# dtb-218-AW1.net
KiCad netlist of a schematic drawn in Altium Designer
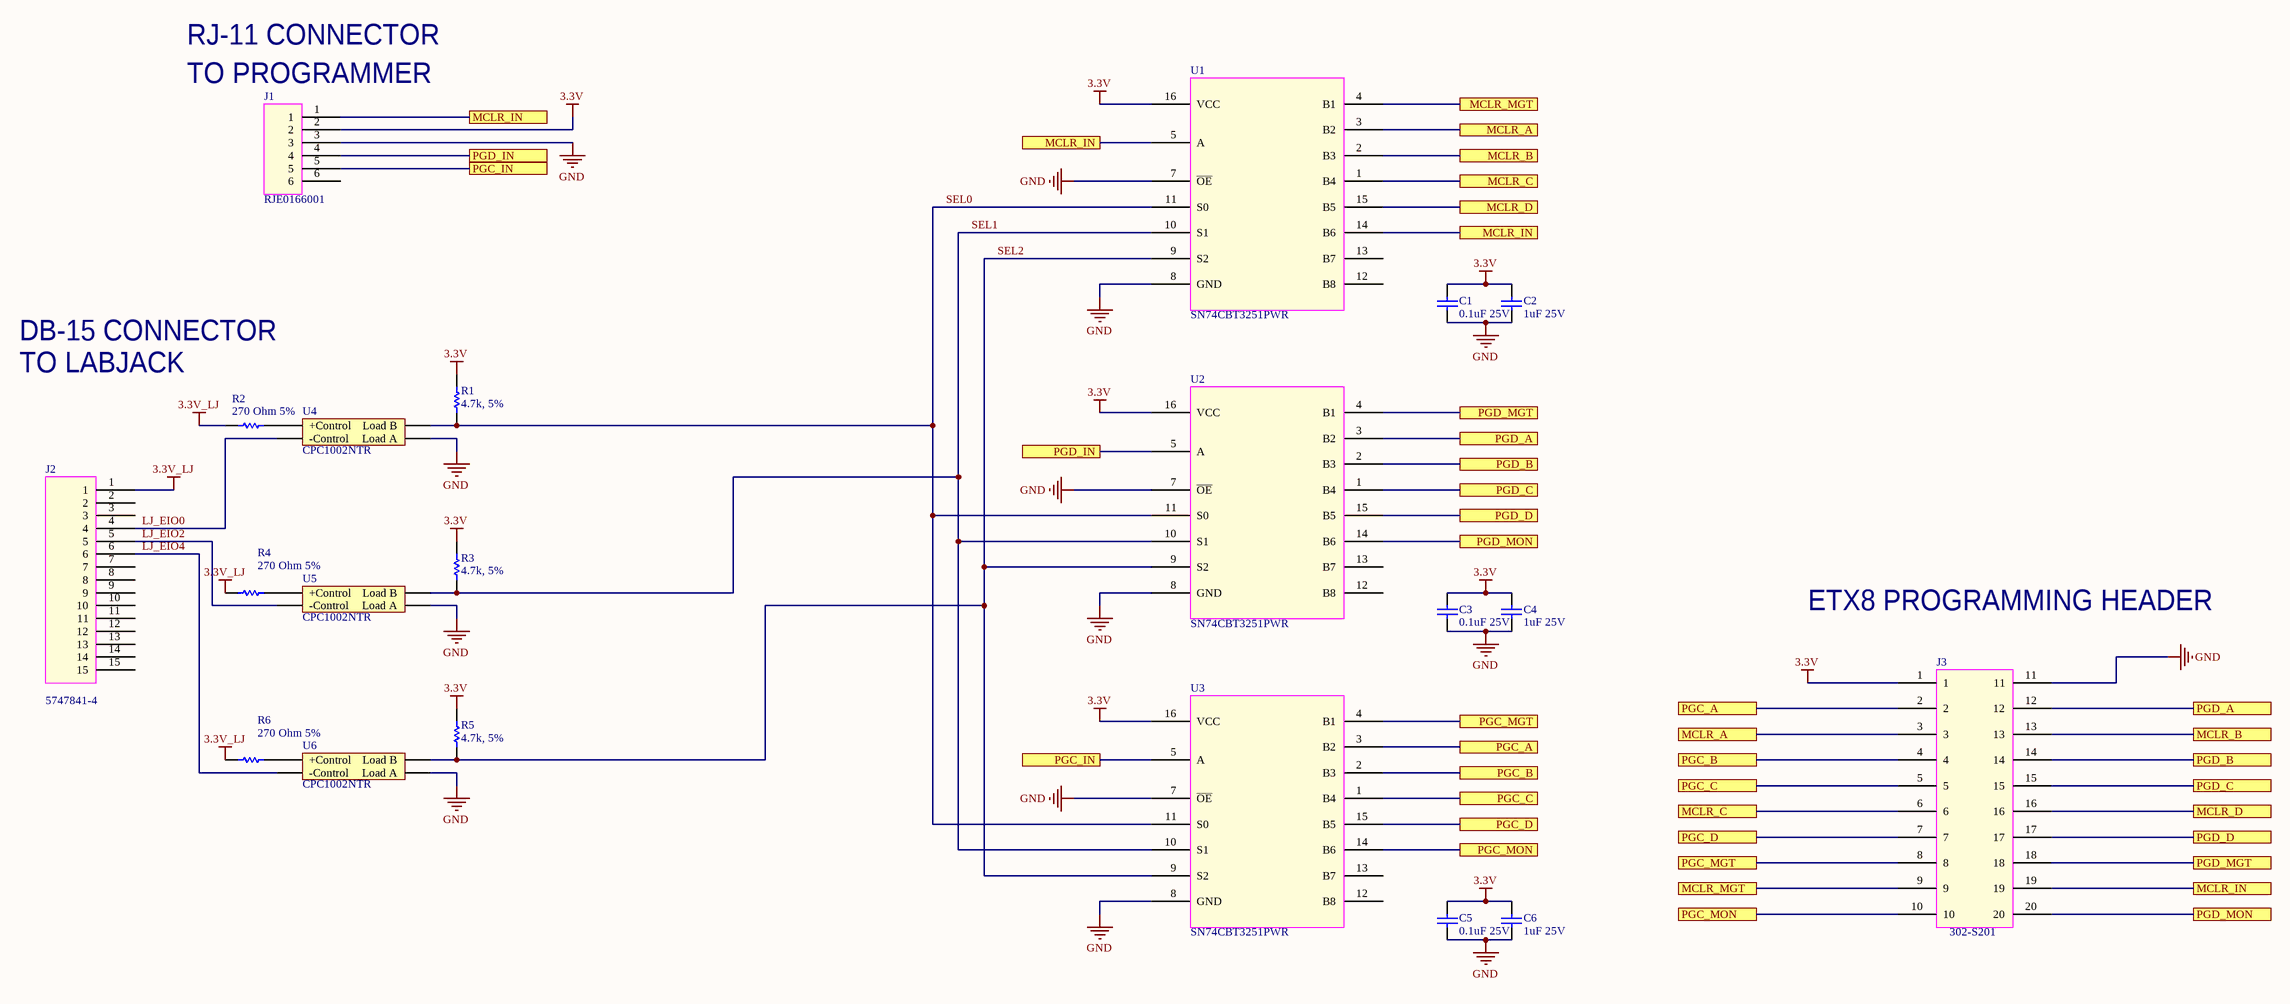
[diagram p0: dtb-218-AW1.SchDoc]

(export (version "E")
  (design (tool "Eeschema 10.0.6"))
  (components
    (comp (ref "C1")
      (value "0.1uF 25V")
      (footprint "Standard VoltServer 0603 Capacitor Footprint")
      (description "CAP CER 0.1UF 25V 10% X7R 0603")
      (fields (field (name "MANUFACTURER") "Samsung") (field (name "Comment") "CL10B104KA8NNNC"))
      (libsource (lib "VoltServer Library") (part "CL10B104KA8NNNC"))
    )
    (comp (ref "C2")
      (value "1uF 25V")
      (footprint "Standard VoltServer 0603 Capacitor Footprint")
      (description "CAP CER 1UF 25V 10% X7R 0603")
      (fields (field (name "MANUFACTURER") "Samsung") (field (name "Comment") "CL10B105KA8NNNC"))
      (libsource (lib "VoltServer Library") (part "CL10B105KA8NNNC"))
    )
    (comp (ref "C3")
      (value "0.1uF 25V")
      (footprint "Standard VoltServer 0603 Capacitor Footprint")
      (description "CAP CER 0.1UF 25V 10% X7R 0603")
      (fields (field (name "MANUFACTURER") "Samsung") (field (name "Comment") "CL10B104KA8NNNC"))
      (libsource (lib "VoltServer Library") (part "CL10B104KA8NNNC"))
    )
    (comp (ref "C4")
      (value "1uF 25V")
      (footprint "Standard VoltServer 0603 Capacitor Footprint")
      (description "CAP CER 1UF 25V 10% X7R 0603")
      (fields (field (name "MANUFACTURER") "Samsung") (field (name "Comment") "CL10B105KA8NNNC"))
      (libsource (lib "VoltServer Library") (part "CL10B105KA8NNNC"))
    )
    (comp (ref "C5")
      (value "0.1uF 25V")
      (footprint "Standard VoltServer 0603 Capacitor Footprint")
      (description "CAP CER 0.1UF 25V 10% X7R 0603")
      (fields (field (name "MANUFACTURER") "Samsung") (field (name "Comment") "CL10B104KA8NNNC"))
      (libsource (lib "VoltServer Library") (part "CL10B104KA8NNNC"))
    )
    (comp (ref "C6")
      (value "1uF 25V")
      (footprint "Standard VoltServer 0603 Capacitor Footprint")
      (description "CAP CER 1UF 25V 10% X7R 0603")
      (fields (field (name "MANUFACTURER") "Samsung") (field (name "Comment") "CL10B105KA8NNNC"))
      (libsource (lib "VoltServer Library") (part "CL10B105KA8NNNC"))
    )
    (comp (ref "J1")
      (value "RJE0166001")
      (footprint "RJE0166001")
      (description "CONN MOD JACK 6P6C R/A UNSHLD")
      (fields (field (name "MANUFACTURER") "Amphenol"))
      (libsource (lib "Allen_Integrated_Library") (part "RJE0166001"))
    )
    (comp (ref "J2")
      (value "5747841-4")
      (footprint "5747841-4")
      (description "CONN D-SUB PLUG 15POS R/A SOLDER")
      (fields (field (name "MANUFACTURER") "TE Connectivity"))
      (libsource (lib "Allen_Integrated_Library") (part "5747841-4"))
    )
    (comp (ref "J3")
      (value "302-S201")
      (footprint "302-S201")
      (description "20 Positions Header, Shrouded Connector 0.100\"")
      (fields (field (name "MANUFACTURER") "On Shore Technology"))
      (libsource (lib "AllenLibrary") (part "302-S201"))
    )
    (comp (ref "R1")
      (value "4.7k, 5%")
      (footprint "Standard VoltServer 0603 Resistor Footprint")
      (description "RES SMD 4.7K OHM 5% 1/10W 0603")
      (fields (field (name "MANUFACTURER") "Samsung") (field (name "Comment") "RC1608J472CS"))
      (libsource (lib "VoltServer Library") (part "RC1608F105CS"))
    )
    (comp (ref "R2")
      (value "270 Ohm 5%")
      (footprint "Standard VoltServer 0603 Resistor Footprint")
      (description "RES SMD 270 OHM 5% 1/10W 0603")
      (fields (field (name "MANUFACTURER") "Samsung") (field (name "Comment") "RC1608J271CS"))
      (libsource (lib "VoltServer Library") (part "RC1608J271CS"))
    )
    (comp (ref "R3")
      (value "4.7k, 5%")
      (footprint "Standard VoltServer 0603 Resistor Footprint")
      (description "RES SMD 4.7K OHM 5% 1/10W 0603")
      (fields (field (name "MANUFACTURER") "Samsung") (field (name "Comment") "RC1608J472CS"))
      (libsource (lib "VoltServer Library") (part "RC1608F105CS"))
    )
    (comp (ref "R4")
      (value "270 Ohm 5%")
      (footprint "Standard VoltServer 0603 Resistor Footprint")
      (description "RES SMD 270 OHM 5% 1/10W 0603")
      (fields (field (name "MANUFACTURER") "Samsung") (field (name "Comment") "RC1608J271CS"))
      (libsource (lib "VoltServer Library") (part "RC1608J271CS"))
    )
    (comp (ref "R5")
      (value "4.7k, 5%")
      (footprint "Standard VoltServer 0603 Resistor Footprint")
      (description "RES SMD 4.7K OHM 5% 1/10W 0603")
      (fields (field (name "MANUFACTURER") "Samsung") (field (name "Comment") "RC1608J472CS"))
      (libsource (lib "VoltServer Library") (part "RC1608F105CS"))
    )
    (comp (ref "R6")
      (value "270 Ohm 5%")
      (footprint "Standard VoltServer 0603 Resistor Footprint")
      (description "RES SMD 270 OHM 5% 1/10W 0603")
      (fields (field (name "MANUFACTURER") "Samsung") (field (name "Comment") "RC1608J271CS"))
      (libsource (lib "VoltServer Library") (part "RC1608J271CS"))
    )
    (comp (ref "U1")
      (value "SN74CBT3251PWR")
      (footprint "SN74CBT3251PWR")
      (description "IC 1-OF-8 FET MUX/DEMUX 16-TSSOP")
      (fields (field (name "MANUFACTURER") "Texas Instruments"))
      (libsource (lib "Allen_Integrated_Library") (part "SN74CBT3251PWR"))
    )
    (comp (ref "U2")
      (value "SN74CBT3251PWR")
      (footprint "SN74CBT3251PWR")
      (description "IC 1-OF-8 FET MUX/DEMUX 16-TSSOP")
      (fields (field (name "MANUFACTURER") "Texas Instruments"))
      (libsource (lib "Allen_Integrated_Library") (part "SN74CBT3251PWR"))
    )
    (comp (ref "U3")
      (value "SN74CBT3251PWR")
      (footprint "SN74CBT3251PWR")
      (description "IC 1-OF-8 FET MUX/DEMUX 16-TSSOP")
      (fields (field (name "MANUFACTURER") "Texas Instruments"))
      (libsource (lib "Allen_Integrated_Library") (part "SN74CBT3251PWR"))
    )
    (comp (ref "U4")
      (value "CPC1002NTR")
      (footprint "CPC1002NTR")
      (description "RELAY OPTOMOS 700MA 4-SOP")
      (fields (field (name "MANUFACTURER") "IXYS Integrated Circuits Division"))
      (libsource (lib "VoltServer Library") (part "CPC1002NTR"))
    )
    (comp (ref "U5")
      (value "CPC1002NTR")
      (footprint "CPC1002NTR")
      (description "RELAY OPTOMOS 700MA 4-SOP")
      (fields (field (name "MANUFACTURER") "IXYS Integrated Circuits Division"))
      (libsource (lib "VoltServer Library") (part "CPC1002NTR"))
    )
    (comp (ref "U6")
      (value "CPC1002NTR")
      (footprint "CPC1002NTR")
      (description "RELAY OPTOMOS 700MA 4-SOP")
      (fields (field (name "MANUFACTURER") "IXYS Integrated Circuits Division"))
      (libsource (lib "VoltServer Library") (part "CPC1002NTR"))
    )
  )
  (nets
    (net (code "1") (name "/LJ_EIO0") (class "Default")
      (node (ref "J2") (pin "4") (pinfunction "4_4") (pintype "passive"))
      (node (ref "U4") (pin "2") (pinfunction "-Control_2") (pintype "passive"))
    )
    (net (code "2") (name "/LJ_EIO2") (class "Default")
      (node (ref "J2") (pin "5") (pinfunction "5_5") (pintype "passive"))
      (node (ref "U5") (pin "2") (pinfunction "-Control_2") (pintype "passive"))
    )
    (net (code "3") (name "/LJ_EIO4") (class "Default")
      (node (ref "J2") (pin "6") (pinfunction "6_6") (pintype "passive"))
      (node (ref "U6") (pin "2") (pinfunction "-Control_2") (pintype "passive"))
    )
    (net (code "4") (name "/MCLR_A") (class "Default")
      (node (ref "J3") (pin "3") (pinfunction "3_3") (pintype "passive"))
      (node (ref "U1") (pin "3") (pinfunction "B2_3") (pintype "passive"))
    )
    (net (code "5") (name "/MCLR_B") (class "Default")
      (node (ref "J3") (pin "13") (pinfunction "13_13") (pintype "passive"))
      (node (ref "U1") (pin "2") (pinfunction "B3_2") (pintype "passive"))
    )
    (net (code "6") (name "/MCLR_C") (class "Default")
      (node (ref "J3") (pin "6") (pinfunction "6_6") (pintype "passive"))
      (node (ref "U1") (pin "1") (pinfunction "B4_1") (pintype "passive"))
    )
    (net (code "7") (name "/MCLR_D") (class "Default")
      (node (ref "J3") (pin "16") (pinfunction "16_16") (pintype "passive"))
      (node (ref "U1") (pin "15") (pinfunction "B5_15") (pintype "passive"))
    )
    (net (code "8") (name "/MCLR_IN") (class "Default")
      (node (ref "J1") (pin "1") (pinfunction "1_1") (pintype "passive"))
      (node (ref "J3") (pin "19") (pinfunction "19_19") (pintype "passive"))
      (node (ref "U1") (pin "14") (pinfunction "B6_14") (pintype "passive"))
      (node (ref "U1") (pin "5") (pinfunction "A_5") (pintype "passive"))
    )
    (net (code "9") (name "/MCLR_MGT") (class "Default")
      (node (ref "J3") (pin "9") (pinfunction "9_9") (pintype "passive"))
      (node (ref "U1") (pin "4") (pinfunction "B1_4") (pintype "passive"))
    )
    (net (code "10") (name "/PGC_A") (class "Default")
      (node (ref "J3") (pin "2") (pinfunction "2_2") (pintype "passive"))
      (node (ref "U3") (pin "3") (pinfunction "B2_3") (pintype "passive"))
    )
    (net (code "11") (name "/PGC_B") (class "Default")
      (node (ref "J3") (pin "4") (pinfunction "4_4") (pintype "passive"))
      (node (ref "U3") (pin "2") (pinfunction "B3_2") (pintype "passive"))
    )
    (net (code "12") (name "/PGC_C") (class "Default")
      (node (ref "J3") (pin "5") (pinfunction "5_5") (pintype "passive"))
      (node (ref "U3") (pin "1") (pinfunction "B4_1") (pintype "passive"))
    )
    (net (code "13") (name "/PGC_D") (class "Default")
      (node (ref "J3") (pin "7") (pinfunction "7_7") (pintype "passive"))
      (node (ref "U3") (pin "15") (pinfunction "B5_15") (pintype "passive"))
    )
    (net (code "14") (name "/PGC_IN") (class "Default")
      (node (ref "J1") (pin "5") (pinfunction "5_5") (pintype "passive"))
      (node (ref "U3") (pin "5") (pinfunction "A_5") (pintype "passive"))
    )
    (net (code "15") (name "/PGC_MGT") (class "Default")
      (node (ref "J3") (pin "8") (pinfunction "8_8") (pintype "passive"))
      (node (ref "U3") (pin "4") (pinfunction "B1_4") (pintype "passive"))
    )
    (net (code "16") (name "/PGC_MON") (class "Default")
      (node (ref "J3") (pin "10") (pinfunction "10_10") (pintype "passive"))
      (node (ref "U3") (pin "14") (pinfunction "B6_14") (pintype "passive"))
    )
    (net (code "17") (name "/PGD_A") (class "Default")
      (node (ref "J3") (pin "12") (pinfunction "12_12") (pintype "passive"))
      (node (ref "U2") (pin "3") (pinfunction "B2_3") (pintype "passive"))
    )
    (net (code "18") (name "/PGD_B") (class "Default")
      (node (ref "J3") (pin "14") (pinfunction "14_14") (pintype "passive"))
      (node (ref "U2") (pin "2") (pinfunction "B3_2") (pintype "passive"))
    )
    (net (code "19") (name "/PGD_C") (class "Default")
      (node (ref "J3") (pin "15") (pinfunction "15_15") (pintype "passive"))
      (node (ref "U2") (pin "1") (pinfunction "B4_1") (pintype "passive"))
    )
    (net (code "20") (name "/PGD_D") (class "Default")
      (node (ref "J3") (pin "17") (pinfunction "17_17") (pintype "passive"))
      (node (ref "U2") (pin "15") (pinfunction "B5_15") (pintype "passive"))
    )
    (net (code "21") (name "/PGD_IN") (class "Default")
      (node (ref "J1") (pin "4") (pinfunction "4_4") (pintype "passive"))
      (node (ref "U2") (pin "5") (pinfunction "A_5") (pintype "passive"))
    )
    (net (code "22") (name "/PGD_MGT") (class "Default")
      (node (ref "J3") (pin "18") (pinfunction "18_18") (pintype "passive"))
      (node (ref "U2") (pin "4") (pinfunction "B1_4") (pintype "passive"))
    )
    (net (code "23") (name "/PGD_MON") (class "Default")
      (node (ref "J3") (pin "20") (pinfunction "20_20") (pintype "passive"))
      (node (ref "U2") (pin "14") (pinfunction "B6_14") (pintype "passive"))
    )
    (net (code "24") (name "/SEL0") (class "Default")
      (node (ref "R1") (pin "2") (pinfunction "2_2") (pintype "passive"))
      (node (ref "U1") (pin "11") (pinfunction "S0_11") (pintype "passive"))
      (node (ref "U2") (pin "11") (pinfunction "S0_11") (pintype "passive"))
      (node (ref "U3") (pin "11") (pinfunction "S0_11") (pintype "passive"))
      (node (ref "U4") (pin "4") (pinfunction "Load_B_4") (pintype "passive"))
    )
    (net (code "25") (name "/SEL1") (class "Default")
      (node (ref "R3") (pin "2") (pinfunction "2_2") (pintype "passive"))
      (node (ref "U1") (pin "10") (pinfunction "S1_10") (pintype "passive"))
      (node (ref "U2") (pin "10") (pinfunction "S1_10") (pintype "passive"))
      (node (ref "U3") (pin "10") (pinfunction "S1_10") (pintype "passive"))
      (node (ref "U5") (pin "4") (pinfunction "Load_B_4") (pintype "passive"))
    )
    (net (code "26") (name "/SEL2") (class "Default")
      (node (ref "R5") (pin "2") (pinfunction "2_2") (pintype "passive"))
      (node (ref "U1") (pin "9") (pinfunction "S2_9") (pintype "passive"))
      (node (ref "U2") (pin "9") (pinfunction "S2_9") (pintype "passive"))
      (node (ref "U3") (pin "9") (pinfunction "S2_9") (pintype "passive"))
      (node (ref "U6") (pin "4") (pinfunction "Load_B_4") (pintype "passive"))
    )
    (net (code "27") (name "3.3V") (class "Default")
      (node (ref "C1") (pin "2") (pinfunction "2_2") (pintype "passive"))
      (node (ref "C2") (pin "2") (pinfunction "2_2") (pintype "passive"))
      (node (ref "C3") (pin "2") (pinfunction "2_2") (pintype "passive"))
      (node (ref "C4") (pin "2") (pinfunction "2_2") (pintype "passive"))
      (node (ref "C5") (pin "2") (pinfunction "2_2") (pintype "passive"))
      (node (ref "C6") (pin "2") (pinfunction "2_2") (pintype "passive"))
      (node (ref "J1") (pin "2") (pinfunction "2_2") (pintype "passive"))
      (node (ref "J3") (pin "1") (pinfunction "1_1") (pintype "passive"))
      (node (ref "R1") (pin "1") (pinfunction "1_1") (pintype "passive"))
      (node (ref "R3") (pin "1") (pinfunction "1_1") (pintype "passive"))
      (node (ref "R5") (pin "1") (pinfunction "1_1") (pintype "passive"))
      (node (ref "U1") (pin "16") (pinfunction "VCC_16") (pintype "passive"))
      (node (ref "U2") (pin "16") (pinfunction "VCC_16") (pintype "passive"))
      (node (ref "U3") (pin "16") (pinfunction "VCC_16") (pintype "passive"))
    )
    (net (code "28") (name "3.3V_LJ") (class "Default")
      (node (ref "J2") (pin "1") (pinfunction "1_1") (pintype "passive"))
      (node (ref "R2") (pin "1") (pinfunction "1_1") (pintype "passive"))
      (node (ref "R4") (pin "1") (pinfunction "1_1") (pintype "passive"))
      (node (ref "R6") (pin "1") (pinfunction "1_1") (pintype "passive"))
    )
    (net (code "29") (name "GND") (class "Default")
      (node (ref "C1") (pin "1") (pinfunction "1_1") (pintype "passive"))
      (node (ref "C2") (pin "1") (pinfunction "1_1") (pintype "passive"))
      (node (ref "C3") (pin "1") (pinfunction "1_1") (pintype "passive"))
      (node (ref "C4") (pin "1") (pinfunction "1_1") (pintype "passive"))
      (node (ref "C5") (pin "1") (pinfunction "1_1") (pintype "passive"))
      (node (ref "C6") (pin "1") (pinfunction "1_1") (pintype "passive"))
      (node (ref "J1") (pin "3") (pinfunction "3_3") (pintype "passive"))
      (node (ref "J3") (pin "11") (pinfunction "11_11") (pintype "passive"))
      (node (ref "U1") (pin "7") (pinfunction "~{OE}_7") (pintype "passive"))
      (node (ref "U1") (pin "8") (pinfunction "GND_8") (pintype "passive"))
      (node (ref "U2") (pin "7") (pinfunction "~{OE}_7") (pintype "passive"))
      (node (ref "U2") (pin "8") (pinfunction "GND_8") (pintype "passive"))
      (node (ref "U3") (pin "7") (pinfunction "~{OE}_7") (pintype "passive"))
      (node (ref "U3") (pin "8") (pinfunction "GND_8") (pintype "passive"))
      (node (ref "U4") (pin "3") (pinfunction "Load_A_3") (pintype "passive"))
      (node (ref "U5") (pin "3") (pinfunction "Load_A_3") (pintype "passive"))
      (node (ref "U6") (pin "3") (pinfunction "Load_A_3") (pintype "passive"))
    )
    (net (code "30") (name "Net-(U4-+Control)") (class "Default")
      (node (ref "R2") (pin "2") (pinfunction "2_2") (pintype "passive"))
      (node (ref "U4") (pin "1") (pinfunction "+Control_1") (pintype "passive"))
    )
    (net (code "31") (name "Net-(U5-+Control)") (class "Default")
      (node (ref "R4") (pin "2") (pinfunction "2_2") (pintype "passive"))
      (node (ref "U5") (pin "1") (pinfunction "+Control_1") (pintype "passive"))
    )
    (net (code "32") (name "Net-(U6-+Control)") (class "Default")
      (node (ref "R6") (pin "2") (pinfunction "2_2") (pintype "passive"))
      (node (ref "U6") (pin "1") (pinfunction "+Control_1") (pintype "passive"))
    )
    (net (code "33") (name "unconnected-(J1-Pad6)") (class "Default")
      (node (ref "J1") (pin "6") (pinfunction "6_6") (pintype "passive"))
    )
    (net (code "34") (name "unconnected-(J2-Pad2)") (class "Default")
      (node (ref "J2") (pin "2") (pinfunction "2_2") (pintype "passive"))
    )
    (net (code "35") (name "unconnected-(J2-Pad3)") (class "Default")
      (node (ref "J2") (pin "3") (pinfunction "3_3") (pintype "passive"))
    )
    (net (code "36") (name "unconnected-(J2-Pad7)") (class "Default")
      (node (ref "J2") (pin "7") (pinfunction "7_7") (pintype "passive"))
    )
    (net (code "37") (name "unconnected-(J2-Pad8)") (class "Default")
      (node (ref "J2") (pin "8") (pinfunction "8_8") (pintype "passive"))
    )
    (net (code "38") (name "unconnected-(J2-Pad9)") (class "Default")
      (node (ref "J2") (pin "9") (pinfunction "9_9") (pintype "passive"))
    )
    (net (code "39") (name "unconnected-(J2-Pad10)") (class "Default")
      (node (ref "J2") (pin "10") (pinfunction "10_10") (pintype "passive"))
    )
    (net (code "40") (name "unconnected-(J2-Pad11)") (class "Default")
      (node (ref "J2") (pin "11") (pinfunction "11_11") (pintype "passive"))
    )
    (net (code "41") (name "unconnected-(J2-Pad12)") (class "Default")
      (node (ref "J2") (pin "12") (pinfunction "12_12") (pintype "passive"))
    )
    (net (code "42") (name "unconnected-(J2-Pad13)") (class "Default")
      (node (ref "J2") (pin "13") (pinfunction "13_13") (pintype "passive"))
    )
    (net (code "43") (name "unconnected-(J2-Pad14)") (class "Default")
      (node (ref "J2") (pin "14") (pinfunction "14_14") (pintype "passive"))
    )
    (net (code "44") (name "unconnected-(J2-Pad15)") (class "Default")
      (node (ref "J2") (pin "15") (pinfunction "15_15") (pintype "passive"))
    )
    (net (code "45") (name "unconnected-(U1-B7-Pad13)") (class "Default")
      (node (ref "U1") (pin "13") (pinfunction "B7_13") (pintype "passive"))
    )
    (net (code "46") (name "unconnected-(U1-B8-Pad12)") (class "Default")
      (node (ref "U1") (pin "12") (pinfunction "B8_12") (pintype "passive"))
    )
    (net (code "47") (name "unconnected-(U2-B7-Pad13)") (class "Default")
      (node (ref "U2") (pin "13") (pinfunction "B7_13") (pintype "passive"))
    )
    (net (code "48") (name "unconnected-(U2-B8-Pad12)") (class "Default")
      (node (ref "U2") (pin "12") (pinfunction "B8_12") (pintype "passive"))
    )
    (net (code "49") (name "unconnected-(U3-B7-Pad13)") (class "Default")
      (node (ref "U3") (pin "13") (pinfunction "B7_13") (pintype "passive"))
    )
    (net (code "50") (name "unconnected-(U3-B8-Pad12)") (class "Default")
      (node (ref "U3") (pin "12") (pinfunction "B8_12") (pintype "passive"))
    )
  )
)
